# Arduino_S3v3_R2.net
KiCad netlist of a schematic drawn in EAGLE
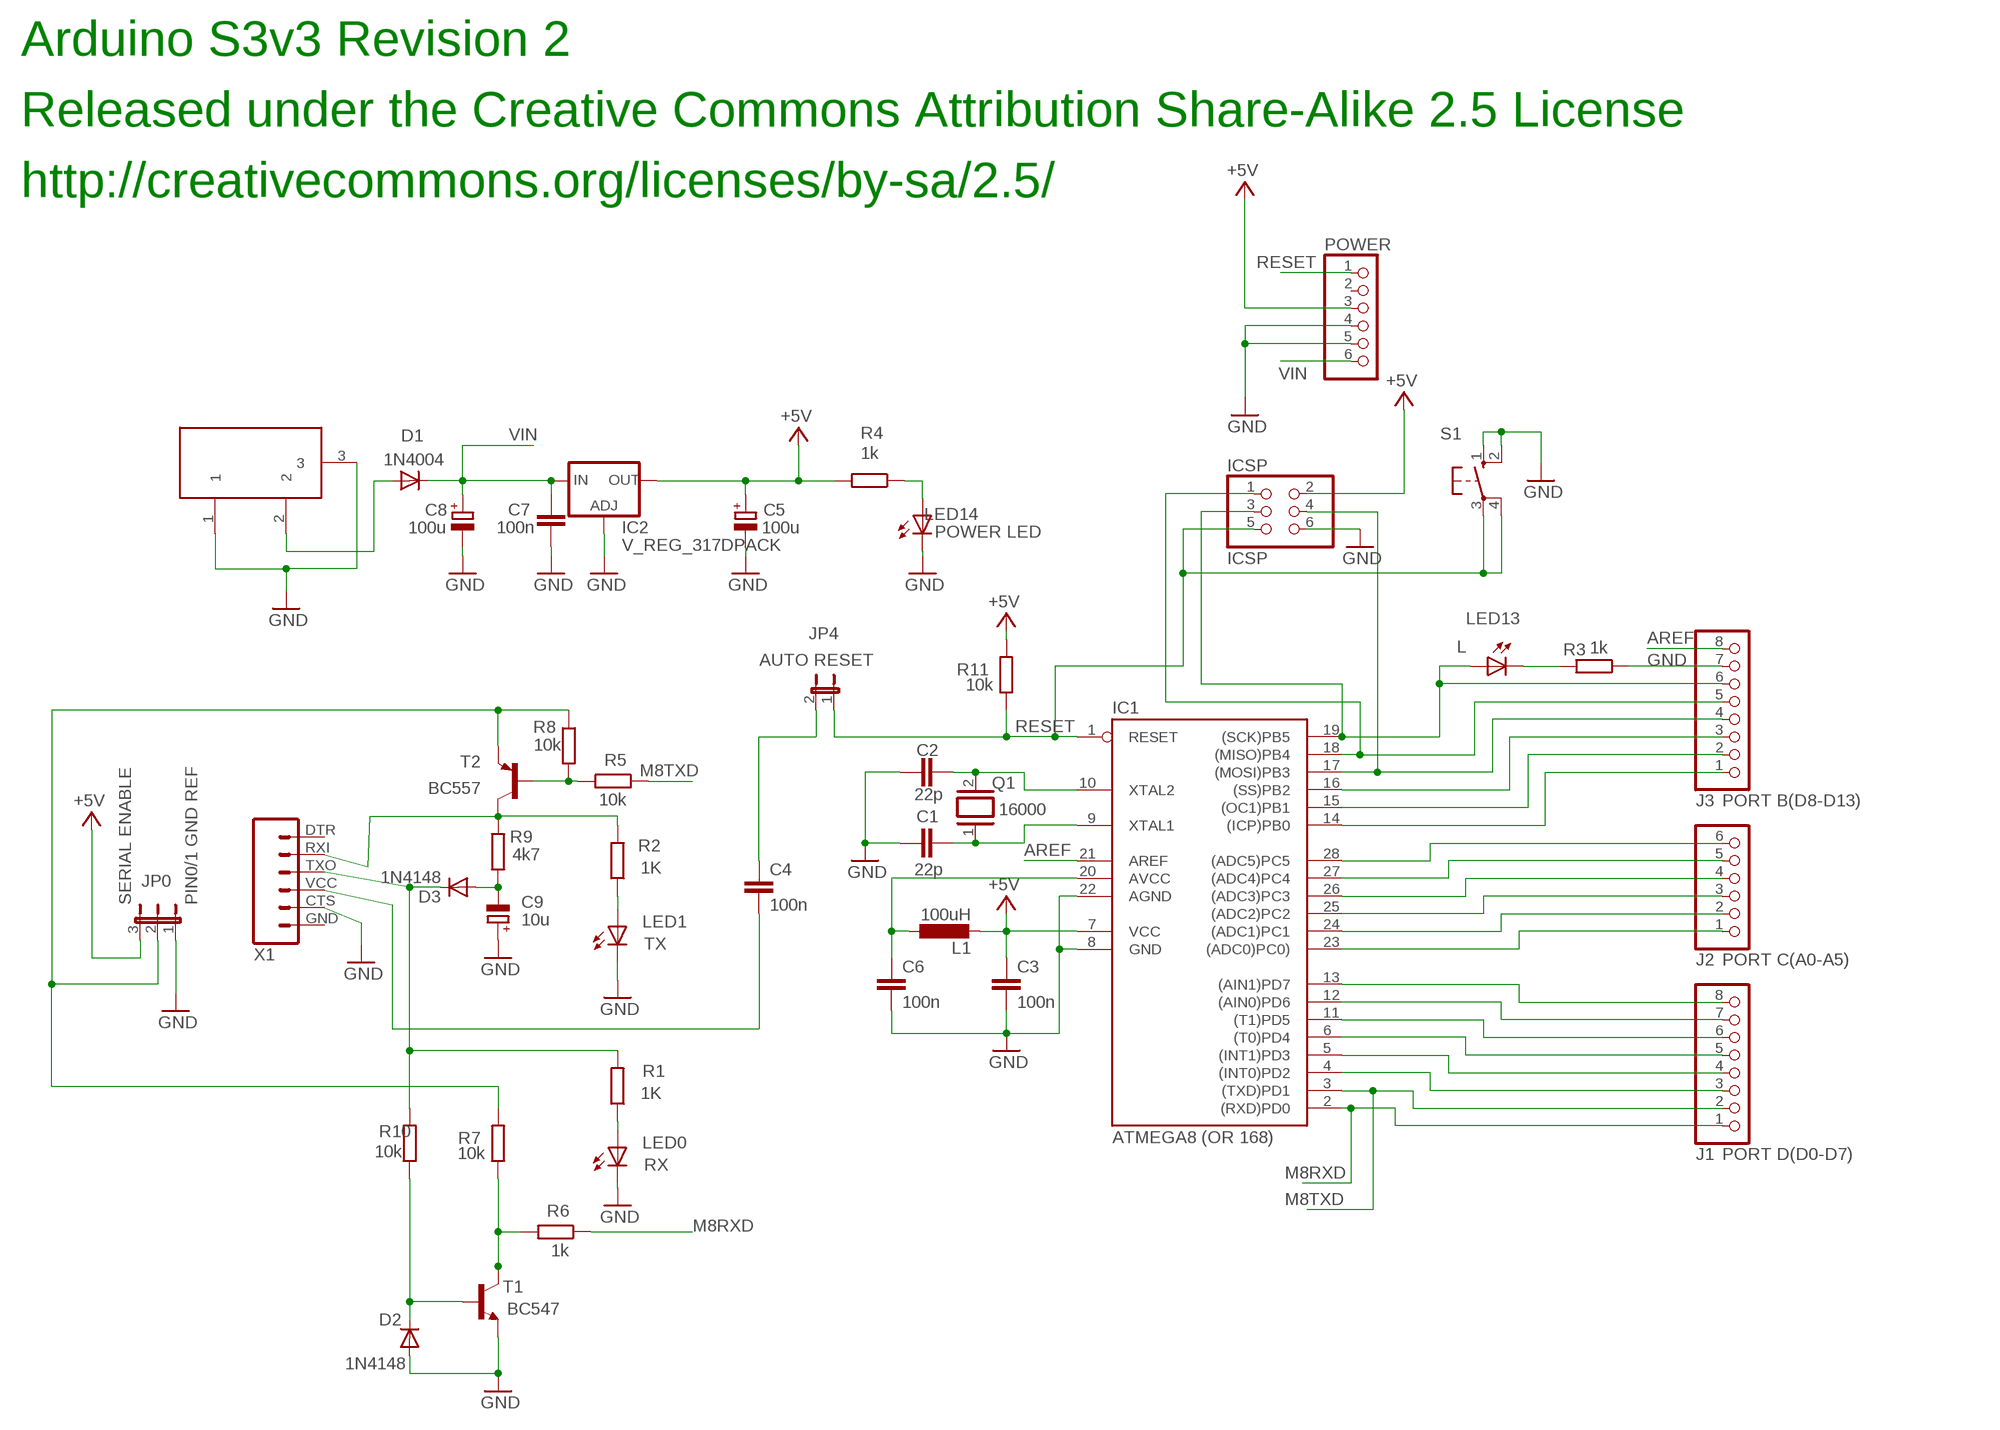
[diagram p0: schematic, sheet 1]

(export (version "E")
  (design (tool "Eeschema 10.0.6"))
  (components
    (comp (ref "C1")
      (value "22p")
      (footprint "eagle-import:C0805")
      (libsource (lib "eagle-import") (part "C-EUC0805"))
    )
    (comp (ref "C2")
      (value "22p")
      (footprint "eagle-import:C0805")
      (libsource (lib "eagle-import") (part "C-EUC0805"))
    )
    (comp (ref "C3")
      (value "100n")
      (footprint "eagle-import:C0805")
      (libsource (lib "eagle-import") (part "C-EUC0805"))
    )
    (comp (ref "C4")
      (value "100n")
      (footprint "eagle-import:C0805")
      (libsource (lib "eagle-import") (part "C-EUC0805"))
    )
    (comp (ref "C5")
      (value "100u")
      (footprint "eagle-import:E3,5-8")
      (libsource (lib "eagle-import") (part "CPOL-EUE3.5-8"))
    )
    (comp (ref "C6")
      (value "100n")
      (footprint "eagle-import:C0805")
      (libsource (lib "eagle-import") (part "C-EUC0805"))
    )
    (comp (ref "C7")
      (value "100n")
      (footprint "eagle-import:C0805")
      (libsource (lib "eagle-import") (part "C-EUC0805"))
    )
    (comp (ref "C8")
      (value "100u")
      (footprint "eagle-import:E3,5-8")
      (libsource (lib "eagle-import") (part "CPOL-EUE3.5-8"))
    )
    (comp (ref "C9")
      (value "10u")
      (footprint "eagle-import:E5-6")
      (libsource (lib "eagle-import") (part "CPOL-EUE5-6"))
    )
    (comp (ref "D1")
      (value "1N4004")
      (footprint "eagle-import:DO41-10")
      (libsource (lib "eagle-import") (part "1N4004"))
    )
    (comp (ref "D2")
      (value "1N4148")
      (footprint "eagle-import:DO35-10")
      (libsource (lib "eagle-import") (part "1N4148"))
    )
    (comp (ref "D3")
      (value "1N4148")
      (footprint "eagle-import:DO35-10")
      (libsource (lib "eagle-import") (part "1N4148"))
    )
    (comp (ref "DC1")
      (value "DC21MMX")
      (footprint "eagle-import:DC-21MM")
      (libsource (lib "eagle-import") (part "DC21MMX"))
    )
    (comp (ref "IC1")
      (value "ATMEGA8 (OR 168)")
      (footprint "eagle-import:DIL28-3")
      (libsource (lib "eagle-import") (part "AT90S4433P"))
    )
    (comp (ref "IC2")
      (value "V_REG_317DPACK")
      (footprint "eagle-import:V-REG_DPACK")
      (libsource (lib "eagle-import") (part "V_REG_317DPACK"))
    )
    (comp (ref "ICSP")
      (value "ICSP")
      (footprint "eagle-import:2X03")
      (libsource (lib "eagle-import") (part "PINHD-2X3"))
    )
    (comp (ref "J1")
      (value "PORT D(D0-D7)")
      (footprint "eagle-import:1X08")
      (libsource (lib "eagle-import") (part "PINHD-1X8"))
    )
    (comp (ref "J2")
      (value "PORT C(A0-A5)")
      (footprint "eagle-import:1X06")
      (libsource (lib "eagle-import") (part "PINHD-1X6"))
    )
    (comp (ref "J3")
      (value "PORT B(D8-D13)")
      (footprint "eagle-import:1X08")
      (libsource (lib "eagle-import") (part "PINHD-1X8"))
    )
    (comp (ref "JP0")
      (value "JP2W")
      (footprint "eagle-import:JP2W")
      (libsource (lib "eagle-import") (part "JP2W"))
    )
    (comp (ref "JP4")
      (value "AUTO RESET")
      (footprint "eagle-import:JP1W")
      (libsource (lib "eagle-import") (part "JP1W"))
    )
    (comp (ref "L1")
      (value "100uH")
      (footprint "eagle-import:L8530M")
      (libsource (lib "eagle-import") (part "L-EUL8530M"))
    )
    (comp (ref "LED0")
      (value "RX")
      (footprint "eagle-import:CHIPLED_0603")
      (libsource (lib "eagle-import") (part "LEDCHIPLED_0603"))
    )
    (comp (ref "LED1")
      (value "TX")
      (footprint "eagle-import:CHIPLED_0603")
      (libsource (lib "eagle-import") (part "LEDCHIPLED_0603"))
    )
    (comp (ref "LED13")
      (value "L")
      (footprint "eagle-import:CHIPLED_0603")
      (libsource (lib "eagle-import") (part "LEDCHIPLED_0603"))
    )
    (comp (ref "LED14")
      (value "POWER LED")
      (footprint "eagle-import:CHIPLED_0603")
      (libsource (lib "eagle-import") (part "LEDCHIPLED_0603"))
    )
    (comp (ref "POWER")
      (value "PINHD-1X6")
      (footprint "eagle-import:1X06")
      (libsource (lib "eagle-import") (part "PINHD-1X6"))
    )
    (comp (ref "Q1")
      (value "16000")
      (footprint "eagle-import:Q")
      (libsource (lib "eagle-import") (part "XTAL"))
    )
    (comp (ref "R1")
      (value "1K")
      (footprint "eagle-import:M0805")
      (libsource (lib "eagle-import") (part "R-EU_M0805"))
    )
    (comp (ref "R2")
      (value "1K")
      (footprint "eagle-import:M0805")
      (libsource (lib "eagle-import") (part "R-EU_M0805"))
    )
    (comp (ref "R3")
      (value "1k")
      (footprint "eagle-import:M0805")
      (libsource (lib "eagle-import") (part "R-EU_M0805"))
    )
    (comp (ref "R4")
      (value "1k")
      (footprint "eagle-import:M0805")
      (libsource (lib "eagle-import") (part "R-EU_M0805"))
    )
    (comp (ref "R5")
      (value "10k")
      (footprint "eagle-import:R0805")
      (libsource (lib "eagle-import") (part "R-EU_R0805"))
    )
    (comp (ref "R6")
      (value "1k")
      (footprint "eagle-import:R0805")
      (libsource (lib "eagle-import") (part "R-EU_R0805"))
    )
    (comp (ref "R7")
      (value "10k")
      (footprint "eagle-import:M0805")
      (libsource (lib "eagle-import") (part "R-EU_M0805"))
    )
    (comp (ref "R8")
      (value "10k")
      (footprint "eagle-import:M0805")
      (libsource (lib "eagle-import") (part "R-EU_M0805"))
    )
    (comp (ref "R9")
      (value "4k7")
      (footprint "eagle-import:M0805")
      (libsource (lib "eagle-import") (part "R-EU_M0805"))
    )
    (comp (ref "R10")
      (value "10k")
      (footprint "eagle-import:M0805")
      (libsource (lib "eagle-import") (part "R-EU_M0805"))
    )
    (comp (ref "R11")
      (value "10k")
      (footprint "eagle-import:M0805")
      (libsource (lib "eagle-import") (part "R-EU_M0805"))
    )
    (comp (ref "S1")
      (value "10-XX")
      (footprint "eagle-import:B3F-10XX")
      (libsource (lib "eagle-import") (part "10-XX"))
    )
    (comp (ref "T1")
      (value "BC547")
      (footprint "eagle-import:TO92")
      (libsource (lib "eagle-import") (part "BC547"))
    )
    (comp (ref "T2")
      (value "BC557")
      (footprint "eagle-import:TO92-EBC")
      (libsource (lib "eagle-import") (part "-PNP-TO92-EBCBC557B"))
    )
    (comp (ref "X1")
      (value "FTDI_BASICPTH")
      (footprint "eagle-import:FTDI_BASIC")
      (libsource (lib "eagle-import") (part "FTDI_BASICPTH"))
    )
  )
  (nets
    (net (code "1") (name "+5V") (class "Default")
      (node (ref "C3") (pin "1") (pinfunction "1_1") (pintype "passive"))
      (node (ref "C5") (pin "+") (pinfunction "+_+") (pintype "passive"))
      (node (ref "IC1") (pin "7") (pinfunction "VCC_7") (pintype "power_in"))
      (node (ref "IC2") (pin "4") (pinfunction "OUT_4") (pintype "output"))
      (node (ref "ICSP") (pin "2") (pinfunction "2_2") (pintype "passive"))
      (node (ref "JP0") (pin "3") (pinfunction "3_3") (pintype "passive"))
      (node (ref "L1") (pin "2") (pinfunction "2_2") (pintype "passive"))
      (node (ref "POWER") (pin "3") (pinfunction "3_3") (pintype "passive"))
      (node (ref "R11") (pin "2") (pinfunction "2_2") (pintype "passive"))
      (node (ref "R4") (pin "2") (pinfunction "2_2") (pintype "passive"))
    )
    (net (code "2") (name "/AREF") (class "Default")
      (node (ref "IC1") (pin "21") (pinfunction "AREF_21") (pintype "power_in"))
      (node (ref "J3") (pin "8") (pinfunction "8_8") (pintype "passive"))
    )
    (net (code "3") (name "/M8RXD") (class "Default")
      (node (ref "IC1") (pin "2") (pinfunction "(RXD)PD0_2") (pintype "bidirectional"))
      (node (ref "J1") (pin "1") (pinfunction "1_1") (pintype "passive"))
      (node (ref "R6") (pin "1") (pinfunction "1_1") (pintype "passive"))
    )
    (net (code "4") (name "/M8TXD") (class "Default")
      (node (ref "IC1") (pin "3") (pinfunction "(TXD)PD1_3") (pintype "bidirectional"))
      (node (ref "J1") (pin "2") (pinfunction "2_2") (pintype "passive"))
      (node (ref "R5") (pin "1") (pinfunction "1_1") (pintype "passive"))
    )
    (net (code "5") (name "/RESET") (class "Default")
      (node (ref "IC1") (pin "1") (pinfunction "RESET_1") (pintype "input"))
      (node (ref "ICSP") (pin "5") (pinfunction "5_5") (pintype "passive"))
      (node (ref "JP4") (pin "1") (pinfunction "1_1") (pintype "passive"))
      (node (ref "POWER") (pin "1") (pinfunction "1_1") (pintype "passive"))
      (node (ref "R11") (pin "1") (pinfunction "1_1") (pintype "passive"))
      (node (ref "S1") (pin "3") (pinfunction "P_3") (pintype "passive"))
      (node (ref "S1") (pin "4") (pinfunction "P1_4") (pintype "passive"))
    )
    (net (code "6") (name "/VIN") (class "Default")
      (node (ref "C7") (pin "2") (pinfunction "2_2") (pintype "passive"))
      (node (ref "C8") (pin "+") (pinfunction "+_+") (pintype "passive"))
      (node (ref "D1") (pin "C") (pinfunction "C_C") (pintype "passive"))
      (node (ref "IC2") (pin "3") (pinfunction "IN_3") (pintype "input"))
      (node (ref "POWER") (pin "6") (pinfunction "6_6") (pintype "passive"))
    )
    (net (code "7") (name "GND") (class "Default")
      (node (ref "C1") (pin "1") (pinfunction "1_1") (pintype "passive"))
      (node (ref "C2") (pin "1") (pinfunction "1_1") (pintype "passive"))
      (node (ref "C3") (pin "2") (pinfunction "2_2") (pintype "passive"))
      (node (ref "C5") (pin "-") (pinfunction "-_-") (pintype "passive"))
      (node (ref "C6") (pin "2") (pinfunction "2_2") (pintype "passive"))
      (node (ref "C7") (pin "1") (pinfunction "1_1") (pintype "passive"))
      (node (ref "C8") (pin "-") (pinfunction "-_-") (pintype "passive"))
      (node (ref "C9") (pin "+") (pinfunction "+_+") (pintype "passive"))
      (node (ref "D2") (pin "A") (pinfunction "A_A") (pintype "passive"))
      (node (ref "DC1") (pin "1") (pinfunction "1_1") (pintype "power_in"))
      (node (ref "DC1") (pin "3") (pinfunction "3_3") (pintype "power_in"))
      (node (ref "IC1") (pin "22") (pinfunction "AGND_22") (pintype "power_in"))
      (node (ref "IC1") (pin "8") (pinfunction "GND_8") (pintype "power_in"))
      (node (ref "IC2") (pin "1") (pinfunction "ADJ_1") (pintype "input"))
      (node (ref "ICSP") (pin "6") (pinfunction "6_6") (pintype "passive"))
      (node (ref "J3") (pin "7") (pinfunction "7_7") (pintype "passive"))
      (node (ref "JP0") (pin "1") (pinfunction "1_1") (pintype "passive"))
      (node (ref "LED0") (pin "C") (pinfunction "C_C") (pintype "passive"))
      (node (ref "LED1") (pin "C") (pinfunction "C_C") (pintype "passive"))
      (node (ref "LED14") (pin "C") (pinfunction "C_C") (pintype "passive"))
      (node (ref "POWER") (pin "4") (pinfunction "4_4") (pintype "passive"))
      (node (ref "POWER") (pin "5") (pinfunction "5_5") (pintype "passive"))
      (node (ref "R3") (pin "1") (pinfunction "1_1") (pintype "passive"))
      (node (ref "S1") (pin "1") (pinfunction "S_1") (pintype "passive"))
      (node (ref "S1") (pin "2") (pinfunction "S1_2") (pintype "passive"))
      (node (ref "T1") (pin "1") (pinfunction "E_1") (pintype "passive"))
      (node (ref "X1") (pin "CTS") (pinfunction "5_CTS") (pintype "passive"))
    )
    (net (code "8") (name "Net-(C4-Pad1)") (class "Default")
      (node (ref "C4") (pin "1") (pinfunction "1_1") (pintype "passive"))
      (node (ref "JP4") (pin "2") (pinfunction "2_2") (pintype "passive"))
    )
    (net (code "9") (name "Net-(C9-Pad-)") (class "Default")
      (node (ref "C9") (pin "-") (pinfunction "-_-") (pintype "passive"))
      (node (ref "D3") (pin "A") (pinfunction "A_A") (pintype "passive"))
      (node (ref "R9") (pin "1") (pinfunction "1_1") (pintype "passive"))
    )
    (net (code "10") (name "Net-(D1-PadA)") (class "Default")
      (node (ref "D1") (pin "A") (pinfunction "A_A") (pintype "passive"))
      (node (ref "DC1") (pin "2") (pinfunction "2_2") (pintype "power_in"))
    )
    (net (code "11") (name "Net-(IC1-(ADC0)PC0))") (class "Default")
      (node (ref "IC1") (pin "23") (pinfunction "(ADC0)PC0)_23") (pintype "bidirectional"))
      (node (ref "J2") (pin "1") (pinfunction "1_1") (pintype "passive"))
    )
    (net (code "12") (name "Net-(IC1-(ADC1)PC1)") (class "Default")
      (node (ref "IC1") (pin "24") (pinfunction "(ADC1)PC1_24") (pintype "bidirectional"))
      (node (ref "J2") (pin "2") (pinfunction "2_2") (pintype "passive"))
    )
    (net (code "13") (name "Net-(IC1-(ADC2)PC2)") (class "Default")
      (node (ref "IC1") (pin "25") (pinfunction "(ADC2)PC2_25") (pintype "bidirectional"))
      (node (ref "J2") (pin "3") (pinfunction "3_3") (pintype "passive"))
    )
    (net (code "14") (name "Net-(IC1-(ADC3)PC3)") (class "Default")
      (node (ref "IC1") (pin "26") (pinfunction "(ADC3)PC3_26") (pintype "bidirectional"))
      (node (ref "J2") (pin "4") (pinfunction "4_4") (pintype "passive"))
    )
    (net (code "15") (name "Net-(IC1-(ADC4)PC4)") (class "Default")
      (node (ref "IC1") (pin "27") (pinfunction "(ADC4)PC4_27") (pintype "bidirectional"))
      (node (ref "J2") (pin "5") (pinfunction "5_5") (pintype "passive"))
    )
    (net (code "16") (name "Net-(IC1-(ADC5)PC5)") (class "Default")
      (node (ref "IC1") (pin "28") (pinfunction "(ADC5)PC5_28") (pintype "bidirectional"))
      (node (ref "J2") (pin "6") (pinfunction "6_6") (pintype "passive"))
    )
    (net (code "17") (name "Net-(IC1-(AIN0)PD6)") (class "Default")
      (node (ref "IC1") (pin "12") (pinfunction "(AIN0)PD6_12") (pintype "bidirectional"))
      (node (ref "J1") (pin "7") (pinfunction "7_7") (pintype "passive"))
    )
    (net (code "18") (name "Net-(IC1-(AIN1)PD7)") (class "Default")
      (node (ref "IC1") (pin "13") (pinfunction "(AIN1)PD7_13") (pintype "bidirectional"))
      (node (ref "J1") (pin "8") (pinfunction "8_8") (pintype "passive"))
    )
    (net (code "19") (name "Net-(IC1-(ICP)PB0)") (class "Default")
      (node (ref "IC1") (pin "14") (pinfunction "(ICP)PB0_14") (pintype "bidirectional"))
      (node (ref "J3") (pin "1") (pinfunction "1_1") (pintype "passive"))
    )
    (net (code "20") (name "Net-(IC1-(INT0)PD2)") (class "Default")
      (node (ref "IC1") (pin "4") (pinfunction "(INT0)PD2_4") (pintype "bidirectional"))
      (node (ref "J1") (pin "3") (pinfunction "3_3") (pintype "passive"))
    )
    (net (code "21") (name "Net-(IC1-(INT1)PD3)") (class "Default")
      (node (ref "IC1") (pin "5") (pinfunction "(INT1)PD3_5") (pintype "bidirectional"))
      (node (ref "J1") (pin "4") (pinfunction "4_4") (pintype "passive"))
    )
    (net (code "22") (name "Net-(IC1-(MISO)PB4)") (class "Default")
      (node (ref "IC1") (pin "18") (pinfunction "(MISO)PB4_18") (pintype "bidirectional"))
      (node (ref "ICSP") (pin "1") (pinfunction "1_1") (pintype "passive"))
      (node (ref "J3") (pin "5") (pinfunction "5_5") (pintype "passive"))
    )
    (net (code "23") (name "Net-(IC1-(MOSI)PB3)") (class "Default")
      (node (ref "IC1") (pin "17") (pinfunction "(MOSI)PB3_17") (pintype "bidirectional"))
      (node (ref "ICSP") (pin "4") (pinfunction "4_4") (pintype "passive"))
      (node (ref "J3") (pin "4") (pinfunction "4_4") (pintype "passive"))
    )
    (net (code "24") (name "Net-(IC1-(OC1)PB1)") (class "Default")
      (node (ref "IC1") (pin "15") (pinfunction "(OC1)PB1_15") (pintype "bidirectional"))
      (node (ref "J3") (pin "2") (pinfunction "2_2") (pintype "passive"))
    )
    (net (code "25") (name "Net-(IC1-(SCK)PB5)") (class "Default")
      (node (ref "IC1") (pin "19") (pinfunction "(SCK)PB5_19") (pintype "bidirectional"))
      (node (ref "ICSP") (pin "3") (pinfunction "3_3") (pintype "passive"))
      (node (ref "J3") (pin "6") (pinfunction "6_6") (pintype "passive"))
      (node (ref "LED13") (pin "A") (pinfunction "A_A") (pintype "passive"))
    )
    (net (code "26") (name "Net-(IC1-(SS)PB2)") (class "Default")
      (node (ref "IC1") (pin "16") (pinfunction "(SS)PB2_16") (pintype "bidirectional"))
      (node (ref "J3") (pin "3") (pinfunction "3_3") (pintype "passive"))
    )
    (net (code "27") (name "Net-(IC1-(T0)PD4)") (class "Default")
      (node (ref "IC1") (pin "6") (pinfunction "(T0)PD4_6") (pintype "bidirectional"))
      (node (ref "J1") (pin "5") (pinfunction "5_5") (pintype "passive"))
    )
    (net (code "28") (name "Net-(IC1-(T1)PD5)") (class "Default")
      (node (ref "IC1") (pin "11") (pinfunction "(T1)PD5_11") (pintype "bidirectional"))
      (node (ref "J1") (pin "6") (pinfunction "6_6") (pintype "passive"))
    )
    (net (code "29") (name "Net-(IC1-AVCC)") (class "Default")
      (node (ref "C6") (pin "1") (pinfunction "1_1") (pintype "passive"))
      (node (ref "IC1") (pin "20") (pinfunction "AVCC_20") (pintype "power_in"))
      (node (ref "L1") (pin "1") (pinfunction "1_1") (pintype "passive"))
    )
    (net (code "30") (name "Net-(IC1-XTAL1)") (class "Default")
      (node (ref "C1") (pin "2") (pinfunction "2_2") (pintype "passive"))
      (node (ref "IC1") (pin "9") (pinfunction "XTAL1_9") (pintype "bidirectional"))
      (node (ref "Q1") (pin "1") (pinfunction "1_1") (pintype "passive"))
    )
    (net (code "31") (name "Net-(IC1-XTAL2)") (class "Default")
      (node (ref "C2") (pin "2") (pinfunction "2_2") (pintype "passive"))
      (node (ref "IC1") (pin "10") (pinfunction "XTAL2_10") (pintype "bidirectional"))
      (node (ref "Q1") (pin "2") (pinfunction "2_2") (pintype "passive"))
    )
    (net (code "32") (name "Net-(JP0-Pad2)") (class "Default")
      (node (ref "JP0") (pin "2") (pinfunction "2_2") (pintype "passive"))
      (node (ref "R7") (pin "2") (pinfunction "2_2") (pintype "passive"))
      (node (ref "R8") (pin "1") (pinfunction "1_1") (pintype "passive"))
      (node (ref "T2") (pin "E") (pinfunction "E_E") (pintype "passive"))
    )
    (net (code "33") (name "Net-(LED0-PadA)") (class "Default")
      (node (ref "LED0") (pin "A") (pinfunction "A_A") (pintype "passive"))
      (node (ref "R1") (pin "1") (pinfunction "1_1") (pintype "passive"))
    )
    (net (code "34") (name "Net-(LED1-PadA)") (class "Default")
      (node (ref "LED1") (pin "A") (pinfunction "A_A") (pintype "passive"))
      (node (ref "R2") (pin "1") (pinfunction "1_1") (pintype "passive"))
    )
    (net (code "35") (name "Net-(LED13-PadC)") (class "Default")
      (node (ref "LED13") (pin "C") (pinfunction "C_C") (pintype "passive"))
      (node (ref "R3") (pin "2") (pinfunction "2_2") (pintype "passive"))
    )
    (net (code "36") (name "Net-(LED14-PadA)") (class "Default")
      (node (ref "LED14") (pin "A") (pinfunction "A_A") (pintype "passive"))
      (node (ref "R4") (pin "1") (pinfunction "1_1") (pintype "passive"))
    )
    (net (code "37") (name "Net-(R5-Pad2)") (class "Default")
      (node (ref "R5") (pin "2") (pinfunction "2_2") (pintype "passive"))
      (node (ref "R8") (pin "2") (pinfunction "2_2") (pintype "passive"))
      (node (ref "T2") (pin "B") (pinfunction "B_B") (pintype "passive"))
    )
    (net (code "38") (name "Net-(T1-B)") (class "Default")
      (node (ref "D2") (pin "C") (pinfunction "C_C") (pintype "passive"))
      (node (ref "R10") (pin "1") (pinfunction "1_1") (pintype "passive"))
      (node (ref "T1") (pin "2") (pinfunction "B_2") (pintype "passive"))
    )
    (net (code "39") (name "Net-(T1-C)") (class "Default")
      (node (ref "R6") (pin "2") (pinfunction "2_2") (pintype "passive"))
      (node (ref "R7") (pin "1") (pinfunction "1_1") (pintype "passive"))
      (node (ref "T1") (pin "3") (pinfunction "C_3") (pintype "passive"))
    )
    (net (code "40") (name "Net-(X1-2)") (class "Default")
      (node (ref "R2") (pin "2") (pinfunction "2_2") (pintype "passive"))
      (node (ref "R9") (pin "2") (pinfunction "2_2") (pintype "passive"))
      (node (ref "T2") (pin "C") (pinfunction "C_C") (pintype "passive"))
      (node (ref "X1") (pin "RXI") (pinfunction "2_RXI") (pintype "passive"))
    )
    (net (code "41") (name "Net-(X1-3)") (class "Default")
      (node (ref "D3") (pin "C") (pinfunction "C_C") (pintype "passive"))
      (node (ref "R1") (pin "2") (pinfunction "2_2") (pintype "passive"))
      (node (ref "R10") (pin "2") (pinfunction "2_2") (pintype "passive"))
      (node (ref "X1") (pin "TXO") (pinfunction "3_TXO") (pintype "passive"))
    )
    (net (code "42") (name "Net-(X1-4)") (class "Default")
      (node (ref "C4") (pin "2") (pinfunction "2_2") (pintype "passive"))
      (node (ref "X1") (pin "VCC") (pinfunction "4_VCC") (pintype "passive"))
    )
    (net (code "43") (name "unconnected-(POWER-Pad2)") (class "Default")
      (node (ref "POWER") (pin "2") (pinfunction "2_2") (pintype "passive"))
    )
    (net (code "44") (name "unconnected-(X1-1-PadDTR)") (class "Default")
      (node (ref "X1") (pin "DTR") (pinfunction "1_DTR") (pintype "passive"))
    )
    (net (code "45") (name "unconnected-(X1-6-PadGND)") (class "Default")
      (node (ref "X1") (pin "GND") (pinfunction "6_GND") (pintype "passive"))
    )
  )
)
